# McPiFace-MiniOled-USBCover-V1.net
KiCad netlist of a schematic drawn in EAGLE
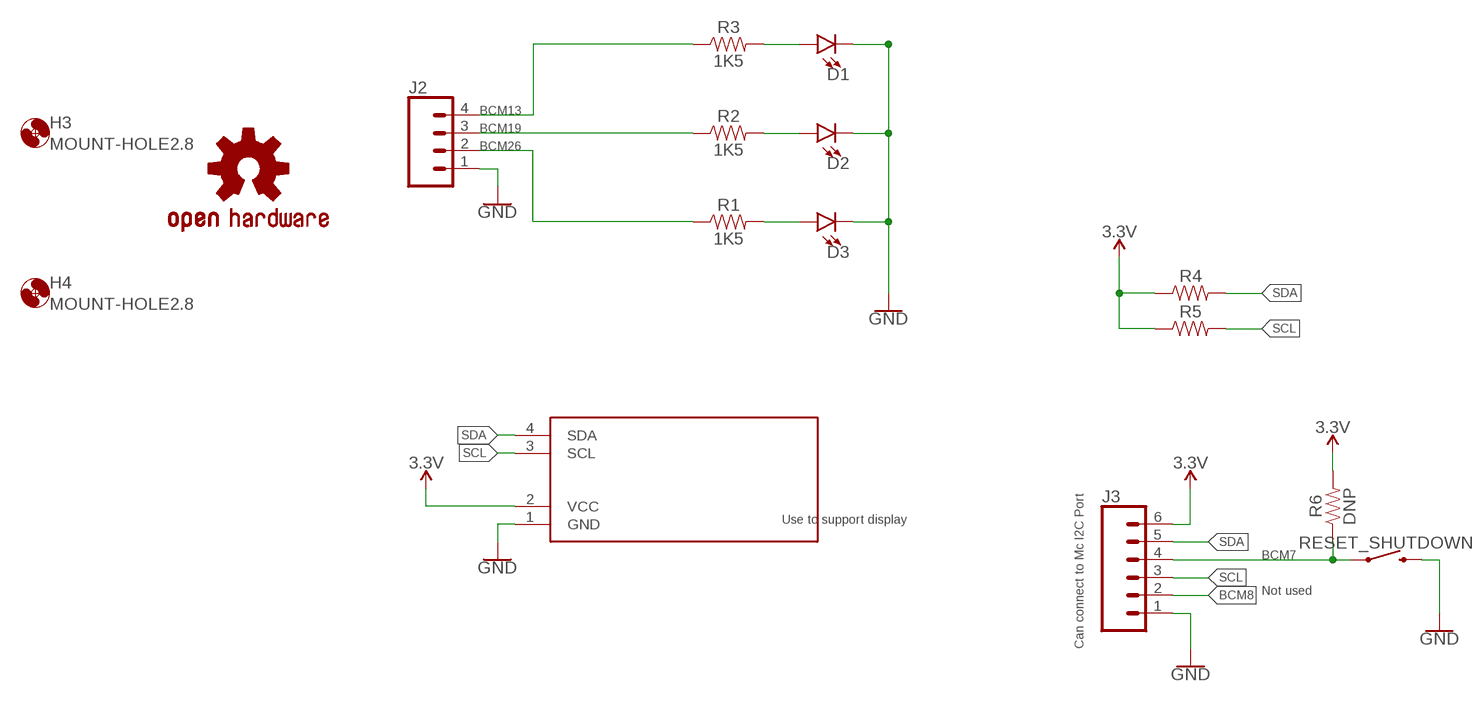
[diagram p0: schematic, sheet 1]

(export (version "E")
  (design (tool "Eeschema 10.0.6"))
  (components
    (comp (ref "D1")
      (value "LED1206-BOTTOM-1.6MM")
      (footprint "eagle-import:LED-1206-BOTTOM-1.6MM")
      (libsource (lib "eagle-import") (part "LED1206-BOTTOM-1.6MM"))
    )
    (comp (ref "D2")
      (value "LED1206-BOTTOM-1.6MM")
      (footprint "eagle-import:LED-1206-BOTTOM-1.6MM")
      (libsource (lib "eagle-import") (part "LED1206-BOTTOM-1.6MM"))
    )
    (comp (ref "D3")
      (value "LED1206-BOTTOM-1.6MM")
      (footprint "eagle-import:LED-1206-BOTTOM-1.6MM")
      (libsource (lib "eagle-import") (part "LED1206-BOTTOM-1.6MM"))
    )
    (comp (ref "DISPLAY")
      (value "DISPLAY0.91_INCH_DISPLAY")
      (footprint "eagle-import:I2C_DISPLAY_0.91_INCH")
      (libsource (lib "eagle-import") (part "DISPLAY0.91_INCH_DISPLAY"))
    )
    (comp (ref "H3")
      (value "MOUNT-HOLE2.8")
      (footprint "eagle-import:2,8")
      (libsource (lib "eagle-import") (part "MOUNT-HOLE2.8"))
    )
    (comp (ref "H4")
      (value "MOUNT-HOLE2.8")
      (footprint "eagle-import:2,8")
      (libsource (lib "eagle-import") (part "MOUNT-HOLE2.8"))
    )
    (comp (ref "J2")
      (value "CONN_04SMD2")
      (footprint "eagle-import:1X04_1MM_RA")
      (libsource (lib "eagle-import") (part "CONN_04SMD2"))
    )
    (comp (ref "J3")
      (value "CONN_06SMD-1MM")
      (footprint "eagle-import:1X06-1MM")
      (libsource (lib "eagle-import") (part "CONN_06SMD-1MM"))
    )
    (comp (ref "LOGO1")
      (value "OSHW-LOGOL")
      (footprint "eagle-import:OSHW-LOGO-L")
      (libsource (lib "eagle-import") (part "OSHW-LOGOL"))
    )
    (comp (ref "R1")
      (value "1K5")
      (footprint "eagle-import:0805")
      (libsource (lib "eagle-import") (part "RESISTOR0805"))
    )
    (comp (ref "R2")
      (value "1K5")
      (footprint "eagle-import:0805")
      (libsource (lib "eagle-import") (part "RESISTOR0805"))
    )
    (comp (ref "R3")
      (value "1K5")
      (footprint "eagle-import:0805")
      (libsource (lib "eagle-import") (part "RESISTOR0805"))
    )
    (comp (ref "R4")
      (value "RESISTOR0805")
      (footprint "eagle-import:0805")
      (libsource (lib "eagle-import") (part "RESISTOR0805"))
    )
    (comp (ref "R5")
      (value "RESISTOR0805")
      (footprint "eagle-import:0805")
      (libsource (lib "eagle-import") (part "RESISTOR0805"))
    )
    (comp (ref "R6")
      (value "DNP")
      (footprint "eagle-import:0805")
      (libsource (lib "eagle-import") (part "RESISTOR0805"))
    )
    (comp (ref "RESET_SHUTDOWN")
      (value "Reset/Powerdown")
      (footprint "eagle-import:TACTILE_SWITCH_PTH_6.0MM_NO_TOP_RESIST")
      (libsource (lib "eagle-import") (part "MOMENTARY-SWITCH-SPSTTACKTILE_SWITCH_PTH_6.0MM_NO_TOP_RESIST"))
    )
  )
  (nets
    (net (code "1") (name "/BCM7") (class "Default")
      (node (ref "J3") (pin "4") (pinfunction "4_4") (pintype "passive"))
      (node (ref "R6") (pin "1") (pinfunction "1_1") (pintype "passive"))
      (node (ref "RESET_SHUTDOWN") (pin "1") (pinfunction "1_1") (pintype "passive"))
    )
    (net (code "2") (name "/BCM13") (class "Default")
      (node (ref "J2") (pin "4") (pinfunction "4_4") (pintype "passive"))
      (node (ref "R3") (pin "1") (pinfunction "1_1") (pintype "passive"))
    )
    (net (code "3") (name "/BCM19") (class "Default")
      (node (ref "J2") (pin "3") (pinfunction "3_3") (pintype "passive"))
      (node (ref "R2") (pin "1") (pinfunction "1_1") (pintype "passive"))
    )
    (net (code "4") (name "/BCM26") (class "Default")
      (node (ref "J2") (pin "2") (pinfunction "2_2") (pintype "passive"))
      (node (ref "R1") (pin "1") (pinfunction "1_1") (pintype "passive"))
    )
    (net (code "5") (name "3.3V") (class "Default")
      (node (ref "DISPLAY") (pin "2") (pinfunction "VCC_2") (pintype "power_in"))
      (node (ref "J3") (pin "6") (pinfunction "6_6") (pintype "passive"))
      (node (ref "R4") (pin "1") (pinfunction "1_1") (pintype "passive"))
      (node (ref "R5") (pin "1") (pinfunction "1_1") (pintype "passive"))
      (node (ref "R6") (pin "2") (pinfunction "2_2") (pintype "passive"))
    )
    (net (code "6") (name "BCM8") (class "Default")
      (node (ref "J3") (pin "2") (pinfunction "2_2") (pintype "passive"))
    )
    (net (code "7") (name "GND") (class "Default")
      (node (ref "D1") (pin "C") (pinfunction "C_C") (pintype "passive"))
      (node (ref "D2") (pin "C") (pinfunction "C_C") (pintype "passive"))
      (node (ref "D3") (pin "C") (pinfunction "C_C") (pintype "passive"))
      (node (ref "DISPLAY") (pin "1") (pinfunction "GND_1") (pintype "power_in"))
      (node (ref "J2") (pin "1") (pinfunction "1_1") (pintype "passive"))
      (node (ref "J3") (pin "1") (pinfunction "1_1") (pintype "passive"))
      (node (ref "RESET_SHUTDOWN") (pin "3") (pinfunction "2_3") (pintype "passive"))
    )
    (net (code "8") (name "Net-(D1-PadA)") (class "Default")
      (node (ref "D1") (pin "A") (pinfunction "A_A") (pintype "passive"))
      (node (ref "R3") (pin "2") (pinfunction "2_2") (pintype "passive"))
    )
    (net (code "9") (name "Net-(D2-PadA)") (class "Default")
      (node (ref "D2") (pin "A") (pinfunction "A_A") (pintype "passive"))
      (node (ref "R2") (pin "2") (pinfunction "2_2") (pintype "passive"))
    )
    (net (code "10") (name "Net-(D3-PadA)") (class "Default")
      (node (ref "D3") (pin "A") (pinfunction "A_A") (pintype "passive"))
      (node (ref "R1") (pin "2") (pinfunction "2_2") (pintype "passive"))
    )
    (net (code "11") (name "SCL") (class "Default")
      (node (ref "DISPLAY") (pin "3") (pinfunction "SCL_3") (pintype "bidirectional"))
      (node (ref "J3") (pin "3") (pinfunction "3_3") (pintype "passive"))
      (node (ref "R5") (pin "2") (pinfunction "2_2") (pintype "passive"))
    )
    (net (code "12") (name "SDA") (class "Default")
      (node (ref "DISPLAY") (pin "4") (pinfunction "SDA_4") (pintype "bidirectional"))
      (node (ref "J3") (pin "5") (pinfunction "5_5") (pintype "passive"))
      (node (ref "R4") (pin "2") (pinfunction "2_2") (pintype "passive"))
    )
  )
)
